# Sheet3.net
KiCad netlist of a schematic drawn in Altium Designer
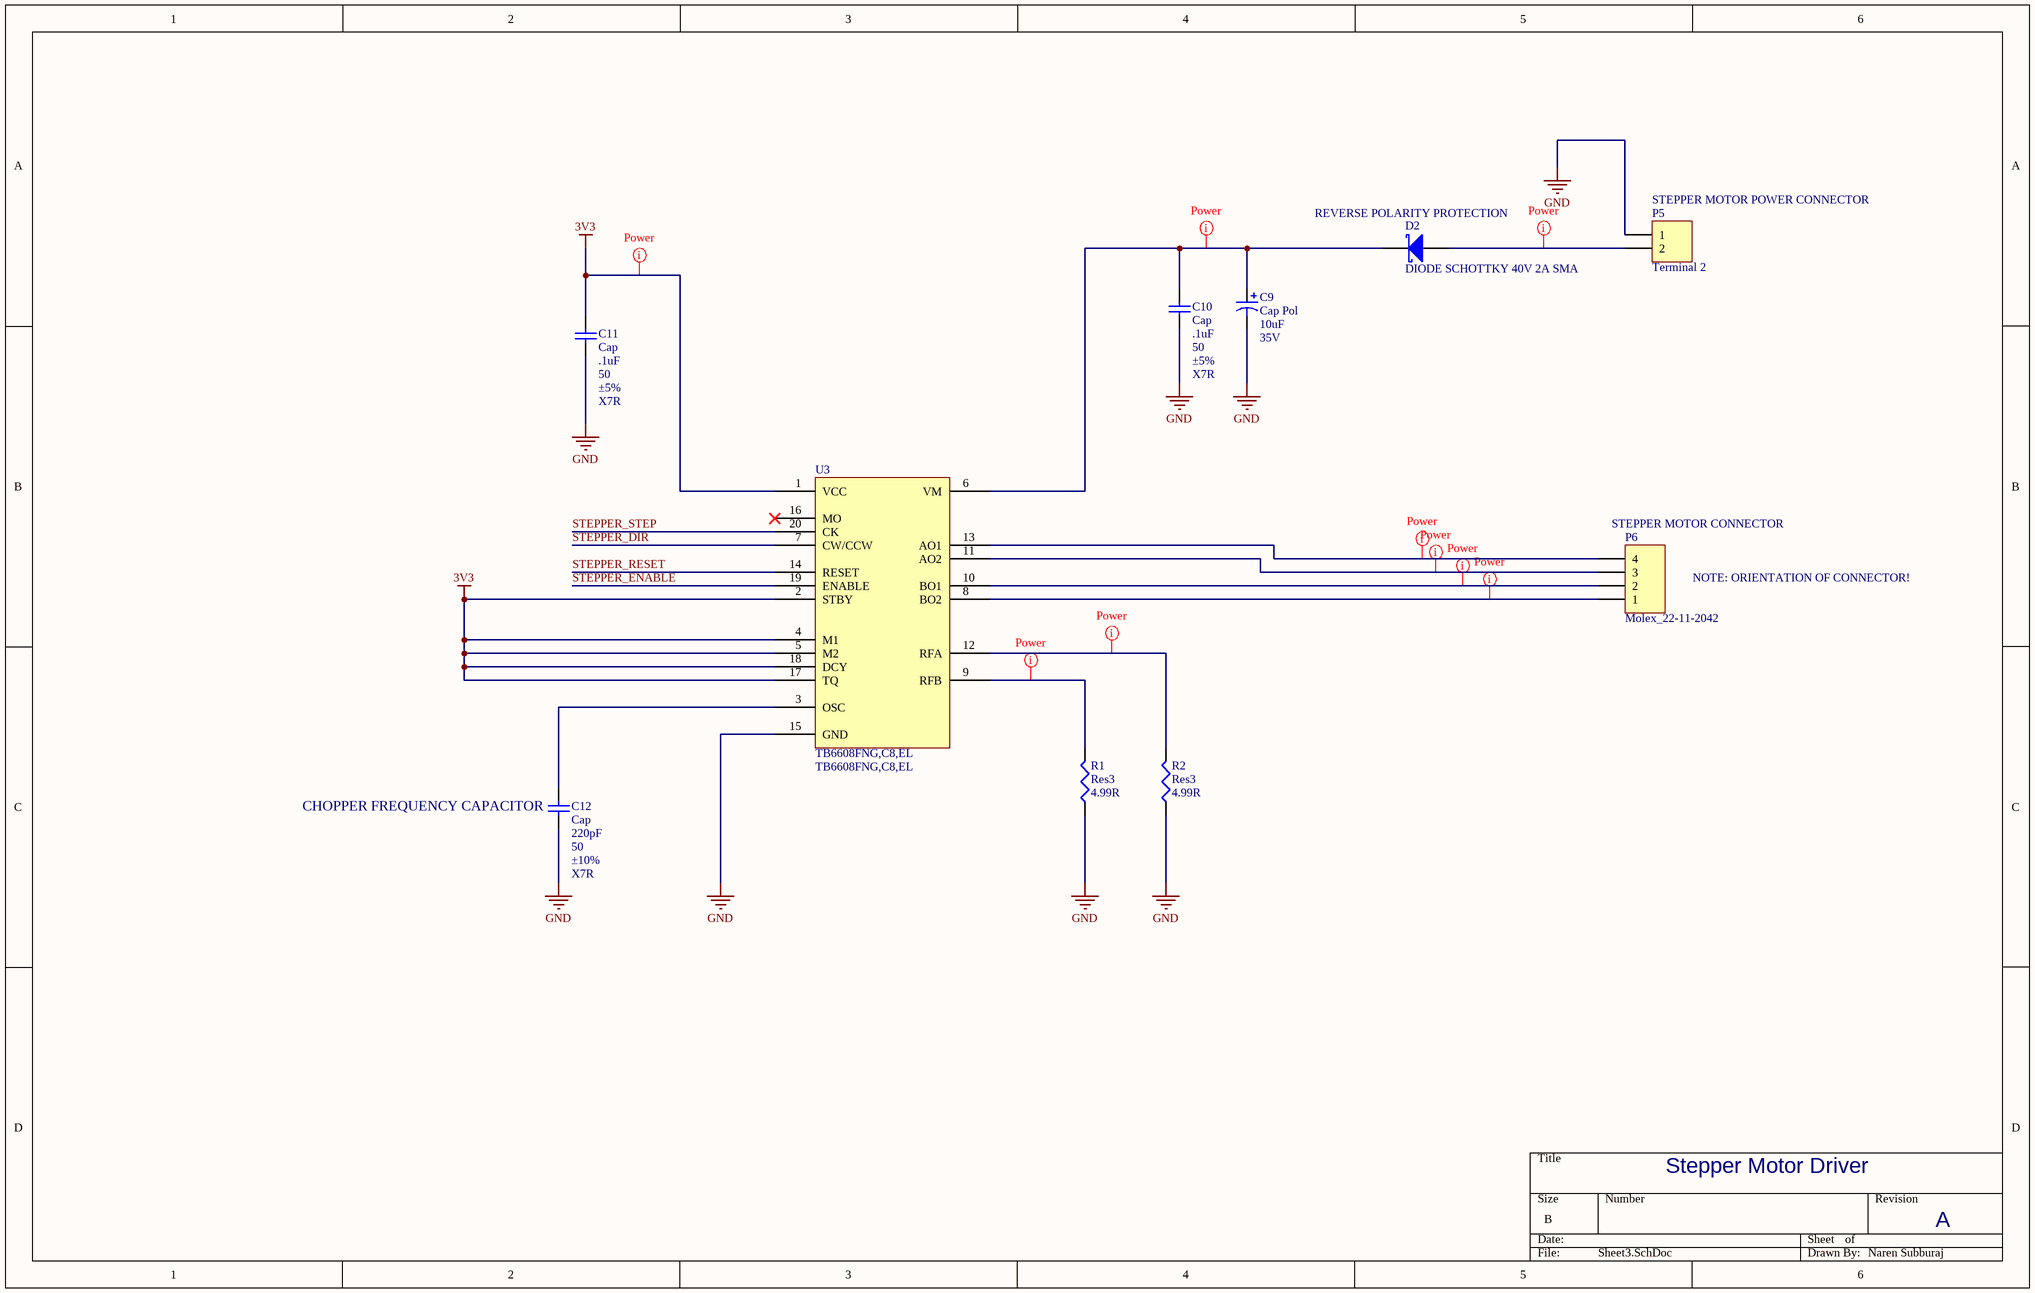
[diagram p0: Sheet3.SchDoc]

(export (version "E")
  (design (tool "Eeschema 10.0.6"))
  (components
    (comp (ref "C9")
      (value "Cap Pol")
      (footprint "CAPACITOR_5MM")
      (description "CAP 85C 10uF ±20% 35V WX Series Aluminum Electrolytic")
      (fields
        (field (name "ALTIUM_VALUE") "10uF")
        (field (name "VOLTAGE") "35V")
        (field (name "MPN") "UWX1V100MCL1GB")
      )
      (libsource (lib "esd_library") (part "Cap Polar-10uF-35V"))
    )
    (comp (ref "C10")
      (value "Cap")
      (footprint "CAPC2012X09M")
      (description "CAP CER .1uF 50v X7R 0805")
      (fields
        (field (name "ALTIUM_VALUE") ".1uF")
        (field (name "WV") "50")
        (field (name "TOLERANCE") "±5%")
        (field (name "TYPE") "X7R")
        (field (name "MPN") "C0805C104J5RACTU")
      )
      (libsource (lib "esd_library") (part "CAP-X7R-.1uF-50V-±5%"))
    )
    (comp (ref "C11")
      (value "Cap")
      (footprint "CAPC2012X09M")
      (description "CAP CER .1uF 50v X7R 0805")
      (fields
        (field (name "ALTIUM_VALUE") ".1uF")
        (field (name "WV") "50")
        (field (name "TOLERANCE") "±5%")
        (field (name "TYPE") "X7R")
        (field (name "MPN") "C0805C104J5RACTU")
      )
      (libsource (lib "esd_library") (part "CAP-X7R-.1uF-50V-±5%"))
    )
    (comp (ref "C12")
      (value "Cap")
      (footprint "CAPC2012X09M")
      (description "CAP CER 220pF 50v X7R 0805")
      (fields
        (field (name "ALTIUM_VALUE") "220pF")
        (field (name "WV") "50")
        (field (name "TOLERANCE") "±10%")
        (field (name "TYPE") "X7R")
        (field (name "MPN") "C0805C221K5RACTU")
      )
      (libsource (lib "esd_library") (part "CAP-X7R-220pF-50V-±10%"))
    )
    (comp (ref "D2")
      (value "DIODE SCHOTTKY 40V 2A SMA")
      (footprint "DIOM4326X23M")
      (description "Schottky Rectifier")
      (fields (field (name "MPN") "B240A-13-F"))
      (libsource (lib "esd_library") (part "DIODE SCHOTTKY 40V 2A SMA"))
    )
    (comp (ref "P5")
      (value "Terminal 2")
      (footprint "TYCO_282841_2")
      (description "Terminal, 2-Pin")
      (fields (field (name "MPN") "282841-2") (field (name "PUBLISHER") "Altium Limited"))
      (libsource (lib "esd_library") (part "Terminal 2"))
    )
    (comp (ref "P6")
      (value "Molex_22-11-2042")
      (footprint "MOLEX-22-11-2042")
      (description "CONN HEADER 4POS .100 VERT GOLD")
      (fields (field (name "MPN") "0022112042"))
      (libsource (lib "esd_library") (part "Molex_22-11-2042"))
    )
    (comp (ref "R1")
      (value "Res3")
      (footprint "RESC2112X05M")
      (description "RES SMD 4.99R OHM 1% 1/8W 0805")
      (fields (field (name "ALTIUM_VALUE") "4.99R") (field (name "MPN") "CRCW08054R99FKEA"))
      (libsource (lib "esd_library") (part "Resistor_4.99R"))
    )
    (comp (ref "R2")
      (value "Res3")
      (footprint "RESC2112X05M")
      (description "RES SMD 4.99R OHM 1% 1/8W 0805")
      (fields (field (name "ALTIUM_VALUE") "4.99R") (field (name "MPN") "CRCW08054R99FKEA"))
      (libsource (lib "esd_library") (part "Resistor_4.99R"))
    )
    (comp (ref "U3")
      (value "TB6608FNG,C8,EL")
      (footprint "TSOP65P640X160-20M")
      (description "IC MTR DRV BIPLR 2.7-5.5V 20SSOP")
      (fields (field (name "MPN") "TB6608FNG,C8,EL"))
      (libsource (lib "esd_library") (part "TB6608FNG,C8,EL"))
    )
  )
  (nets
    (net (code "1") (name "/STEPPER_DIR") (class "Default")
      (node (ref "U3") (pin "7") (pinfunction "CW/CCW_7") (pintype "passive"))
    )
    (net (code "2") (name "/STEPPER_ENABLE") (class "Default")
      (node (ref "U3") (pin "19") (pinfunction "ENABLE_19") (pintype "passive"))
    )
    (net (code "3") (name "/STEPPER_RESET") (class "Default")
      (node (ref "U3") (pin "14") (pinfunction "RESET_14") (pintype "passive"))
    )
    (net (code "4") (name "/STEPPER_STEP") (class "Default")
      (node (ref "U3") (pin "20") (pinfunction "CK_20") (pintype "passive"))
    )
    (net (code "5") (name "3V3") (class "Default")
      (node (ref "C11") (pin "1") (pinfunction "1_1") (pintype "passive"))
      (node (ref "U3") (pin "1") (pinfunction "VCC_1") (pintype "passive"))
      (node (ref "U3") (pin "17") (pinfunction "TQ_17") (pintype "passive"))
      (node (ref "U3") (pin "18") (pinfunction "DCY_18") (pintype "passive"))
      (node (ref "U3") (pin "2") (pinfunction "STBY_2") (pintype "passive"))
      (node (ref "U3") (pin "4") (pinfunction "M1_4") (pintype "passive"))
      (node (ref "U3") (pin "5") (pinfunction "M2_5") (pintype "passive"))
    )
    (net (code "6") (name "GND") (class "Default")
      (node (ref "C10") (pin "2") (pinfunction "2_2") (pintype "passive"))
      (node (ref "C11") (pin "2") (pinfunction "2_2") (pintype "passive"))
      (node (ref "C12") (pin "2") (pinfunction "2_2") (pintype "passive"))
      (node (ref "C9") (pin "2") (pinfunction "2_2") (pintype "passive"))
      (node (ref "P5") (pin "1") (pinfunction "1_1") (pintype "passive"))
      (node (ref "R1") (pin "1") (pinfunction "1_1") (pintype "passive"))
      (node (ref "R2") (pin "1") (pinfunction "1_1") (pintype "passive"))
      (node (ref "U3") (pin "15") (pinfunction "GND_15") (pintype "passive"))
    )
    (net (code "7") (name "Net-(D2-A)") (class "Default")
      (node (ref "D2") (pin "2") (pinfunction "A_2") (pintype "passive"))
      (node (ref "P5") (pin "2") (pinfunction "2_2") (pintype "passive"))
    )
    (net (code "8") (name "Net-(D2-K)") (class "Default")
      (node (ref "C10") (pin "1") (pinfunction "1_1") (pintype "passive"))
      (node (ref "C9") (pin "1") (pinfunction "1_1") (pintype "passive"))
      (node (ref "D2") (pin "1") (pinfunction "K_1") (pintype "passive"))
      (node (ref "U3") (pin "6") (pinfunction "VM_6") (pintype "passive"))
    )
    (net (code "9") (name "Net-(U3-AO1)") (class "Default")
      (node (ref "P6") (pin "4") (pinfunction "4_4") (pintype "passive"))
      (node (ref "U3") (pin "13") (pinfunction "AO1_13") (pintype "passive"))
    )
    (net (code "10") (name "Net-(U3-AO2)") (class "Default")
      (node (ref "P6") (pin "3") (pinfunction "3_3") (pintype "passive"))
      (node (ref "U3") (pin "11") (pinfunction "AO2_11") (pintype "passive"))
    )
    (net (code "11") (name "Net-(U3-BO1)") (class "Default")
      (node (ref "P6") (pin "2") (pinfunction "2_2") (pintype "passive"))
      (node (ref "U3") (pin "10") (pinfunction "BO1_10") (pintype "passive"))
    )
    (net (code "12") (name "Net-(U3-BO2)") (class "Default")
      (node (ref "P6") (pin "1") (pinfunction "1_1") (pintype "passive"))
      (node (ref "U3") (pin "8") (pinfunction "BO2_8") (pintype "passive"))
    )
    (net (code "13") (name "Net-(U3-OSC)") (class "Default")
      (node (ref "C12") (pin "1") (pinfunction "1_1") (pintype "passive"))
      (node (ref "U3") (pin "3") (pinfunction "OSC_3") (pintype "passive"))
    )
    (net (code "14") (name "Net-(U3-RFA)") (class "Default")
      (node (ref "R2") (pin "2") (pinfunction "2_2") (pintype "passive"))
      (node (ref "U3") (pin "12") (pinfunction "RFA_12") (pintype "passive"))
    )
    (net (code "15") (name "Net-(U3-RFB)") (class "Default")
      (node (ref "R1") (pin "2") (pinfunction "2_2") (pintype "passive"))
      (node (ref "U3") (pin "9") (pinfunction "RFB_9") (pintype "passive"))
    )
    (net (code "16") (name "unconnected-(U3-MO-Pad16)") (class "Default")
      (node (ref "U3") (pin "16") (pinfunction "MO_16") (pintype "passive+no_connect"))
    )
  )
)
